# SCH_LIGA2026_2026-04-17.net
KiCad netlist of a schematic drawn in EasyEDA
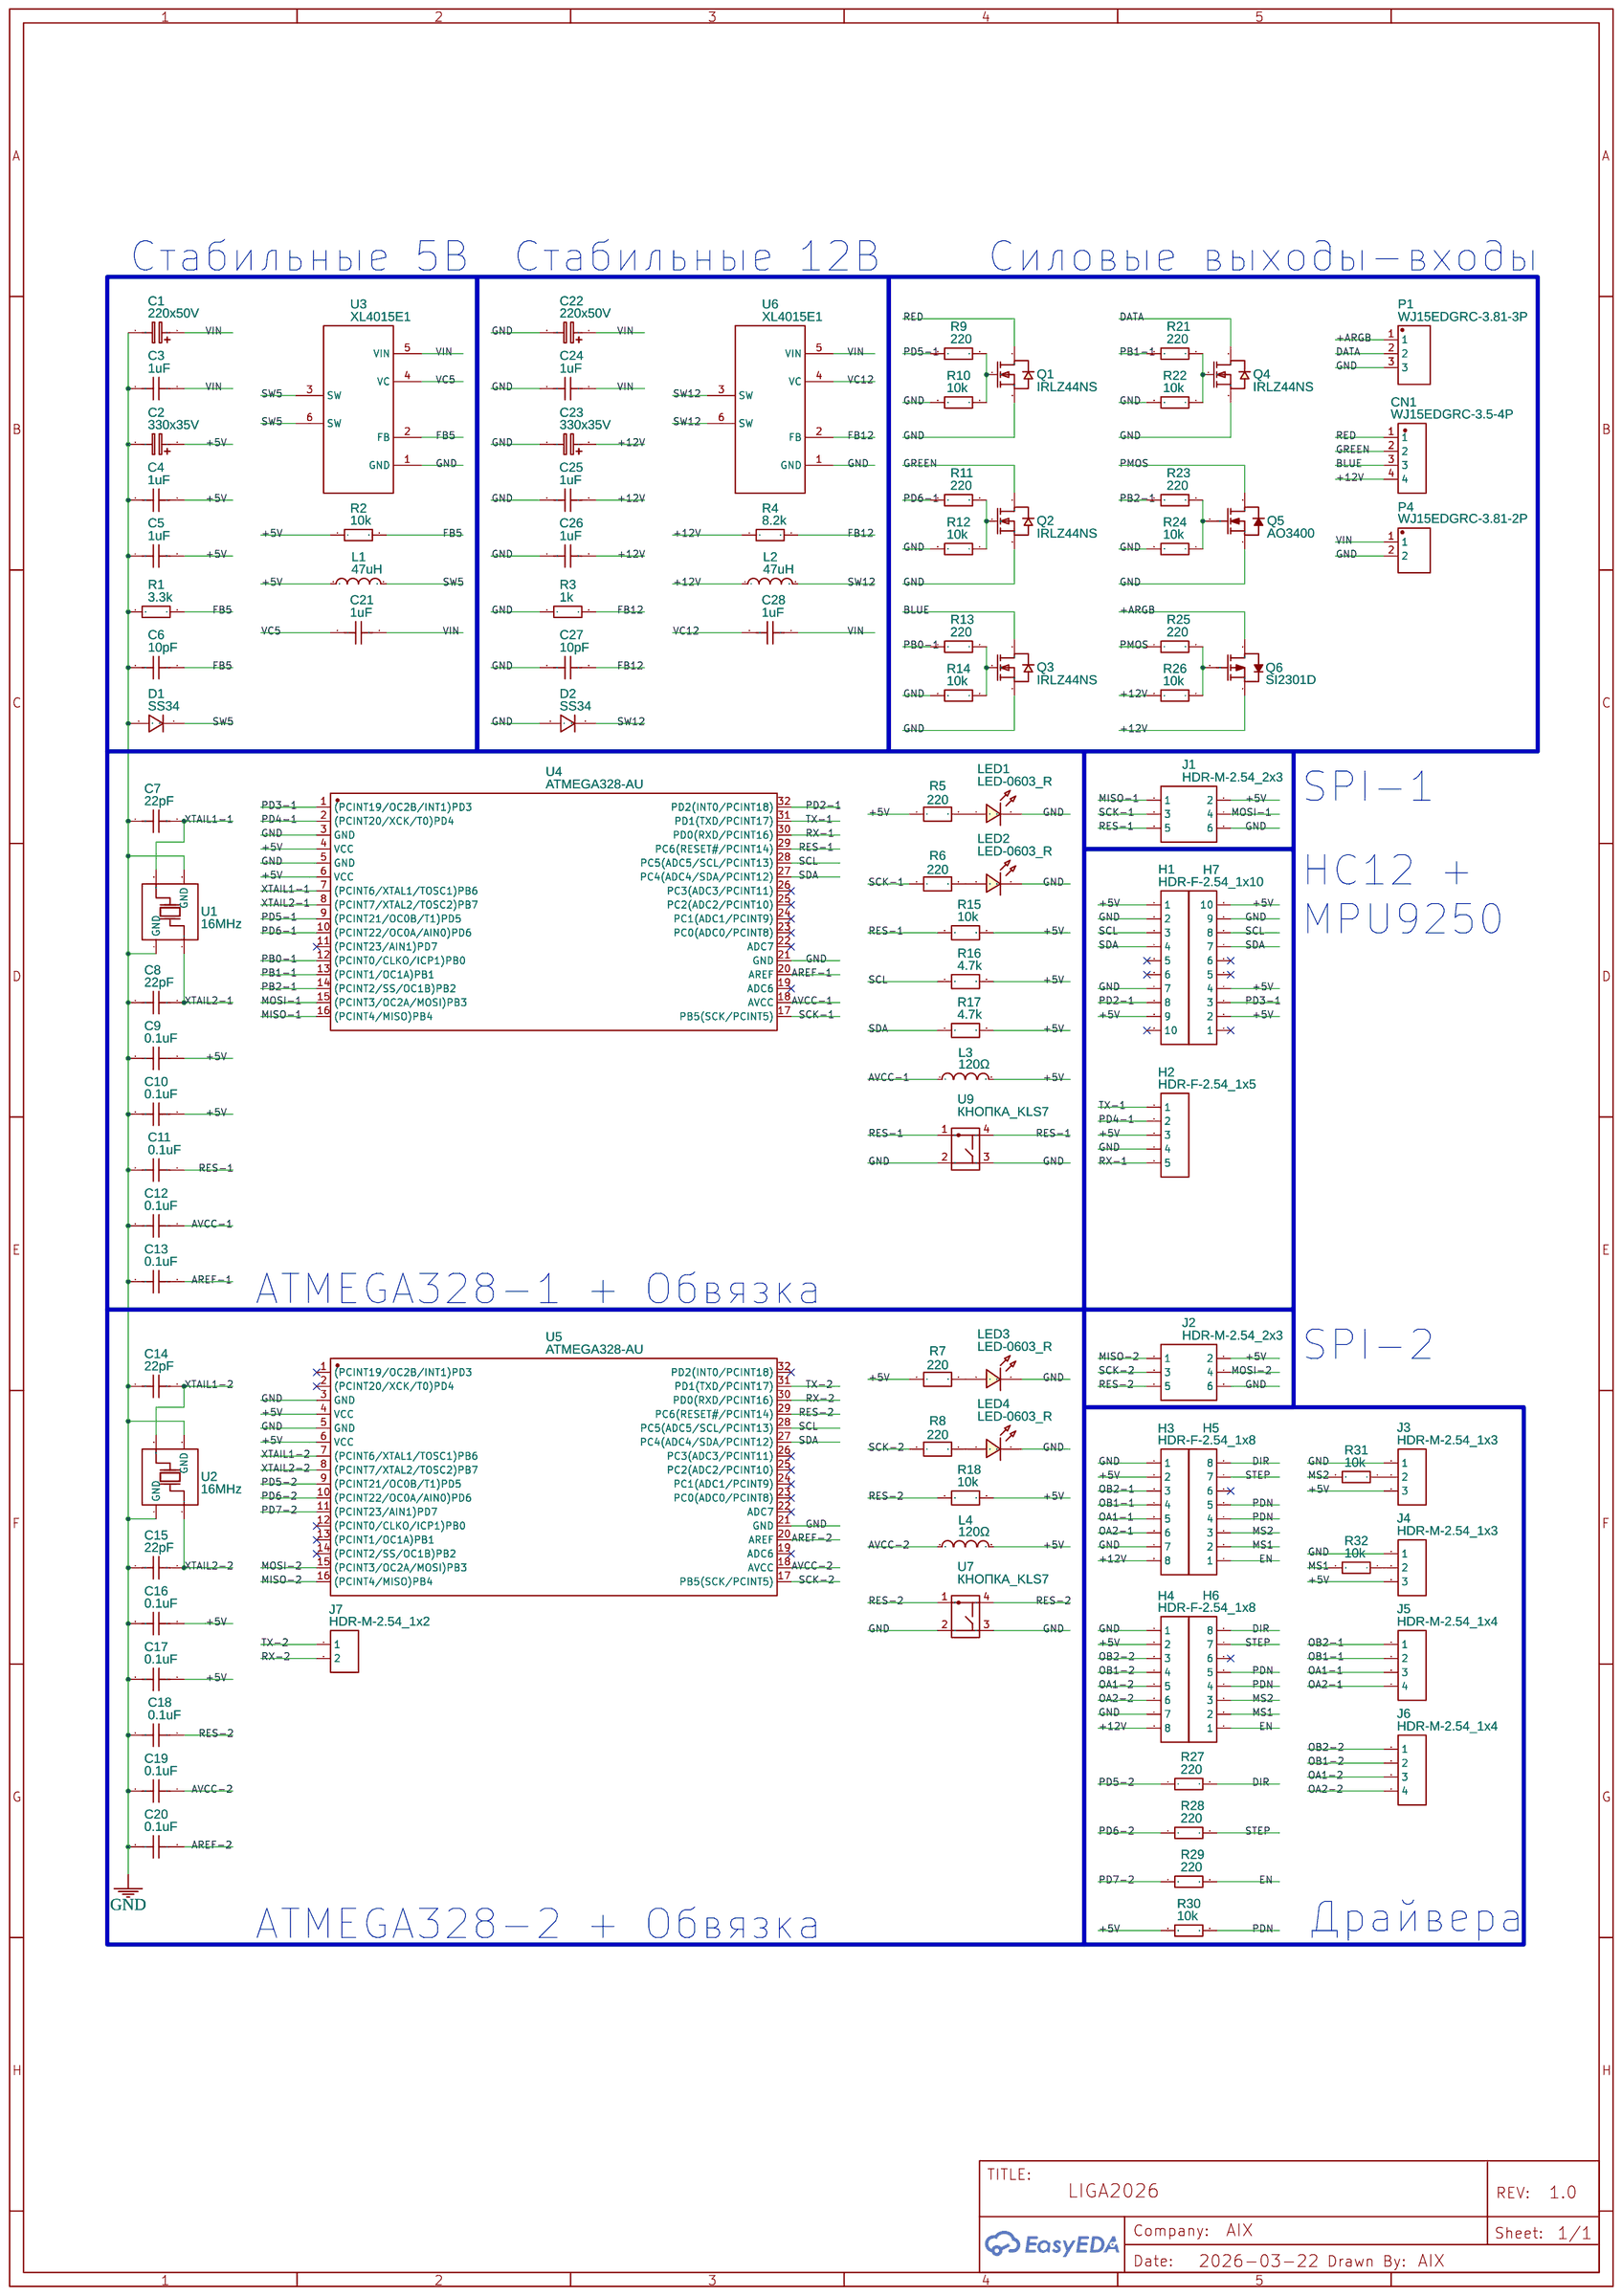
[diagram p0: schematic sheet]

(export (version "E")
  (design (tool "Eeschema 10.0.6"))
  (components
    (comp (ref "C1")
      (value "220x50V")
      (fields (field (name "Manufacturer Part") "330uF 35V (ECAP)"))
      (libsource (lib "") (part "ECAP_SMD_10X10.5"))
    )
    (comp (ref "C2")
      (value "330x35V")
      (fields (field (name "Manufacturer Part") "330uF 35V (ECAP)"))
      (libsource (lib "") (part "ECAP_SMD_10X10.5"))
    )
    (comp (ref "C3")
      (value "1uF")
      (fields (field (name "Manufacturer Part") "0805"))
      (libsource (lib "") (part "0805_C9900012713"))
    )
    (comp (ref "C4")
      (value "1uF")
      (fields (field (name "Manufacturer Part") "0805"))
      (libsource (lib "") (part "0805_C9900012713"))
    )
    (comp (ref "C5")
      (value "1uF")
      (fields (field (name "Manufacturer Part") "0805"))
      (libsource (lib "") (part "0805_C9900012713_1"))
    )
    (comp (ref "C6")
      (value "10pF")
      (fields
        (field (name "Manufacturer Part") "CSA0603C0G100J500JT")
        (field (name "Manufacturer") "HRE(芯声)")
      )
      (libsource (lib "") (part "CSA0603C0G100J500JT"))
    )
    (comp (ref "C7") (value "22pF") (libsource (lib "") (part "C_0603_US_1")))
    (comp (ref "C8") (value "22pF") (libsource (lib "") (part "C_0603_US_1")))
    (comp (ref "C9") (value "0.1uF") (libsource (lib "") (part "C_0603_US")))
    (comp (ref "C10") (value "0.1uF") (libsource (lib "") (part "C_0603_US")))
    (comp (ref "C11") (value "0.1uF") (libsource (lib "") (part "C_0603_US")))
    (comp (ref "C12") (value "0.1uF") (libsource (lib "") (part "C_0603_US")))
    (comp (ref "C13") (value "0.1uF") (libsource (lib "") (part "C_0603_US")))
    (comp (ref "C14") (value "22pF") (libsource (lib "") (part "C_0603_US_1")))
    (comp (ref "C15") (value "22pF") (libsource (lib "") (part "C_0603_US_1")))
    (comp (ref "C16") (value "0.1uF") (libsource (lib "") (part "C_0603_US")))
    (comp (ref "C17") (value "0.1uF") (libsource (lib "") (part "C_0603_US")))
    (comp (ref "C18") (value "0.1uF") (libsource (lib "") (part "C_0603_US")))
    (comp (ref "C19") (value "0.1uF") (libsource (lib "") (part "C_0603_US")))
    (comp (ref "C20") (value "0.1uF") (libsource (lib "") (part "C_0603_US")))
    (comp (ref "C21")
      (value "1uF")
      (fields (field (name "Manufacturer Part") "0805"))
      (libsource (lib "") (part "0805_C9900012713"))
    )
    (comp (ref "C22")
      (value "220x50V")
      (fields (field (name "Manufacturer Part") "330uF 35V (ECAP)"))
      (libsource (lib "") (part "ECAP_SMD_10X10.5_1"))
    )
    (comp (ref "C23")
      (value "330x35V")
      (fields (field (name "Manufacturer Part") "330uF 35V (ECAP)"))
      (libsource (lib "") (part "ECAP_SMD_10X10.5_1"))
    )
    (comp (ref "C24")
      (value "1uF")
      (fields (field (name "Manufacturer Part") "0805"))
      (libsource (lib "") (part "0805_C9900012713"))
    )
    (comp (ref "C25")
      (value "1uF")
      (fields (field (name "Manufacturer Part") "0805"))
      (libsource (lib "") (part "0805_C9900012713"))
    )
    (comp (ref "C26")
      (value "1uF")
      (fields (field (name "Manufacturer Part") "0805"))
      (libsource (lib "") (part "0805_C9900012713_1"))
    )
    (comp (ref "C27")
      (value "10pF")
      (fields
        (field (name "Manufacturer Part") "CSA0603C0G100J500JT")
        (field (name "Manufacturer") "HRE(芯声)")
      )
      (libsource (lib "") (part "CSA0603C0G100J500JT"))
    )
    (comp (ref "C28")
      (value "1uF")
      (fields (field (name "Manufacturer Part") "0805"))
      (libsource (lib "") (part "0805_C9900012713"))
    )
    (comp (ref "CN1")
      (value "WJ15EDGRC-3.5-4P")
      (fields (field (name "Manufacturer") "KANGNEX(康奈克斯电气)"))
      (libsource (lib "") (part "WJ15EDGRC-3.5-4P"))
    )
    (comp (ref "D1")
      (value "SS34")
      (fields (field (name "Manufacturer Part") "1N4007W") (field (name "Manufacturer") "BLUE ROCKET"))
      (libsource (lib "") (part "1N4007W"))
    )
    (comp (ref "D2")
      (value "SS34")
      (fields (field (name "Manufacturer Part") "1N4007W") (field (name "Manufacturer") "BLUE ROCKET"))
      (libsource (lib "") (part "1N4007W"))
    )
    (comp (ref "H1") (value "HDR-F-2.54_1x10") (libsource (lib "") (part "HDR-F-2.54_1x10_1")))
    (comp (ref "H2") (value "HDR-F-2.54_1x5") (libsource (lib "") (part "HDR-F-2.54_1x5")))
    (comp (ref "H3") (value "HDR-F-2.54_1x8") (libsource (lib "") (part "HDR-F-2.54_1x8")))
    (comp (ref "H4") (value "HDR-F-2.54_1x8") (libsource (lib "") (part "HDR-F-2.54_1x8")))
    (comp (ref "H5") (value "HDR-F-2.54_1x8") (libsource (lib "") (part "HDR-F-2.54_1x8_1")))
    (comp (ref "H6") (value "HDR-F-2.54_1x8") (libsource (lib "") (part "HDR-F-2.54_1x8_1")))
    (comp (ref "H7") (value "HDR-F-2.54_1x10") (libsource (lib "") (part "HDR-F-2.54_1x10")))
    (comp (ref "J1") (value "HDR-M-2.54_2x3") (libsource (lib "") (part "HDR-M-2.54_2x3")))
    (comp (ref "J2") (value "HDR-M-2.54_2x3") (libsource (lib "") (part "HDR-M-2.54_2x3")))
    (comp (ref "J3") (value "HDR-M-2.54_1x3") (libsource (lib "") (part "HDR-M-2.54_1x3")))
    (comp (ref "J4") (value "HDR-M-2.54_1x3") (libsource (lib "") (part "HDR-M-2.54_1x3")))
    (comp (ref "J5") (value "HDR-M-2.54_1x4") (libsource (lib "") (part "HDR-M-2.54_1x4")))
    (comp (ref "J6") (value "HDR-M-2.54_1x4") (libsource (lib "") (part "HDR-M-2.54_1x4")))
    (comp (ref "J7") (value "HDR-M-2.54_1x2") (libsource (lib "") (part "HDR-M-2.54_1x2")))
    (comp (ref "L1")
      (value "47uH")
      (fields (field (name "Manufacturer Part") "MDE1040-2R2M") (field (name "Manufacturer") "KOHERelec(科或)"))
      (libsource (lib "") (part "MDE1040-2R2M"))
    )
    (comp (ref "L2")
      (value "47uH")
      (fields (field (name "Manufacturer Part") "MDE1040-2R2M") (field (name "Manufacturer") "KOHERelec(科或)"))
      (libsource (lib "") (part "MDE1040-2R2M"))
    )
    (comp (ref "L3")
      (value "120Ω")
      (fields (field (name "Manufacturer Part") "BLM21PG121SN1D") (field (name "Manufacturer") "muRata(村田)"))
      (libsource (lib "") (part "BLM21PG121SN1D"))
    )
    (comp (ref "L4")
      (value "120Ω")
      (fields (field (name "Manufacturer Part") "BLM21PG121SN1D") (field (name "Manufacturer") "muRata(村田)"))
      (libsource (lib "") (part "BLM21PG121SN1D"))
    )
    (comp (ref "LED1")
      (value "LED-0603_R")
      (fields
        (field (name "Manufacturer Part") "19-217/R6C-AL1M2VY/3T")
        (field (name "Manufacturer") "EVERLIGHT(台湾亿光)")
      )
      (libsource (lib "") (part "LED-0603_R"))
    )
    (comp (ref "LED2")
      (value "LED-0603_R")
      (fields
        (field (name "Manufacturer Part") "19-217/R6C-AL1M2VY/3T")
        (field (name "Manufacturer") "EVERLIGHT(台湾亿光)")
      )
      (libsource (lib "") (part "LED-0603_R"))
    )
    (comp (ref "LED3")
      (value "LED-0603_R")
      (fields
        (field (name "Manufacturer Part") "19-217/R6C-AL1M2VY/3T")
        (field (name "Manufacturer") "EVERLIGHT(台湾亿光)")
      )
      (libsource (lib "") (part "LED-0603_R_1"))
    )
    (comp (ref "LED4")
      (value "LED-0603_R")
      (fields
        (field (name "Manufacturer Part") "19-217/R6C-AL1M2VY/3T")
        (field (name "Manufacturer") "EVERLIGHT(台湾亿光)")
      )
      (libsource (lib "") (part "LED-0603_R_1"))
    )
    (comp (ref "P1")
      (value "WJ15EDGRC-3.81-3P")
      (fields
        (field (name "Manufacturer Part") "WJ15EDGRC-3.81-03P-14-00A")
        (field (name "Manufacturer") "KANGNEX(康奈克斯电气)")
      )
      (libsource (lib "") (part "WJ15EDGRC-3.81-3P"))
    )
    (comp (ref "P4")
      (value "WJ15EDGRC-3.81-2P")
      (fields
        (field (name "Manufacturer Part") "WJ15EDGRC-3.81-02P-14-00A")
        (field (name "Manufacturer") "KANGNEX(康奈克斯电气)")
      )
      (libsource (lib "") (part "WJ15EDGRC-3.81-2P"))
    )
    (comp (ref "Q1")
      (value "IRLZ44NS")
      (fields
        (field (name "Manufacturer Part") "IRLZ44NSTRL(UMW)")
        (field (name "Manufacturer") "UMW(友台半导体)")
      )
      (libsource (lib "") (part "IRLZ44NSTRL(UMW)"))
    )
    (comp (ref "Q2")
      (value "IRLZ44NS")
      (fields
        (field (name "Manufacturer Part") "IRLZ44NSTRL(UMW)")
        (field (name "Manufacturer") "UMW(友台半导体)")
      )
      (libsource (lib "") (part "IRLZ44NSTRL(UMW)"))
    )
    (comp (ref "Q3")
      (value "IRLZ44NS")
      (fields
        (field (name "Manufacturer Part") "IRLZ44NSTRL(UMW)")
        (field (name "Manufacturer") "UMW(友台半导体)")
      )
      (libsource (lib "") (part "IRLZ44NSTRL(UMW)"))
    )
    (comp (ref "Q4")
      (value "IRLZ44NS")
      (fields
        (field (name "Manufacturer Part") "IRLZ44NSTRL(UMW)")
        (field (name "Manufacturer") "UMW(友台半导体)")
      )
      (libsource (lib "") (part "IRLZ44NSTRL(UMW)"))
    )
    (comp (ref "Q5")
      (value "AO3400")
      (fields (field (name "Manufacturer Part") "AO3400A") (field (name "Manufacturer") "ChipNobo(无边界)"))
      (libsource (lib "") (part "AO3400A_C42419946"))
    )
    (comp (ref "Q6")
      (value "SI2301D")
      (fields (field (name "Manufacturer Part") "SI2301DS-ES") (field (name "Manufacturer") "ElecSuper(静芯)"))
      (libsource (lib "") (part "SI2301DS-ES"))
    )
    (comp (ref "R1")
      (value "3.3k")
      (fields (field (name "Manufacturer Part") "0805"))
      (libsource (lib "") (part "0805_C9900012714"))
    )
    (comp (ref "R2")
      (value "10k")
      (fields (field (name "Manufacturer Part") "0805"))
      (libsource (lib "") (part "0805_C9900012714"))
    )
    (comp (ref "R3")
      (value "1k")
      (fields (field (name "Manufacturer Part") "0805"))
      (libsource (lib "") (part "0805_C9900012714"))
    )
    (comp (ref "R4")
      (value "8.2k")
      (fields (field (name "Manufacturer Part") "0805"))
      (libsource (lib "") (part "0805_C9900012714"))
    )
    (comp (ref "R5") (value "220") (libsource (lib "") (part "R_0603_EU")))
    (comp (ref "R6") (value "220") (libsource (lib "") (part "R_0603_EU")))
    (comp (ref "R7") (value "220") (libsource (lib "") (part "R_0603_EU")))
    (comp (ref "R8") (value "220") (libsource (lib "") (part "R_0603_EU")))
    (comp (ref "R9")
      (value "220")
      (fields (field (name "Manufacturer Part") "0805"))
      (libsource (lib "") (part "0805_C9900012714"))
    )
    (comp (ref "R10")
      (value "10k")
      (fields (field (name "Manufacturer Part") "0805"))
      (libsource (lib "") (part "0805_C9900012714_1"))
    )
    (comp (ref "R11")
      (value "220")
      (fields (field (name "Manufacturer Part") "0805"))
      (libsource (lib "") (part "0805_C9900012714"))
    )
    (comp (ref "R12")
      (value "10k")
      (fields (field (name "Manufacturer Part") "0805"))
      (libsource (lib "") (part "0805_C9900012714_1"))
    )
    (comp (ref "R13")
      (value "220")
      (fields (field (name "Manufacturer Part") "0805"))
      (libsource (lib "") (part "0805_C9900012714"))
    )
    (comp (ref "R14")
      (value "10k")
      (fields (field (name "Manufacturer Part") "0805"))
      (libsource (lib "") (part "0805_C9900012714_1"))
    )
    (comp (ref "R15") (value "10k") (libsource (lib "") (part "R_0603_EU")))
    (comp (ref "R16") (value "4.7k") (libsource (lib "") (part "R_0603_EU")))
    (comp (ref "R17") (value "4.7k") (libsource (lib "") (part "R_0603_EU")))
    (comp (ref "R18") (value "10k") (libsource (lib "") (part "R_0603_EU")))
    (comp (ref "R21")
      (value "220")
      (fields (field (name "Manufacturer Part") "0805"))
      (libsource (lib "") (part "0805_C9900012714"))
    )
    (comp (ref "R22")
      (value "10k")
      (fields (field (name "Manufacturer Part") "0805"))
      (libsource (lib "") (part "0805_C9900012714_1"))
    )
    (comp (ref "R23")
      (value "220")
      (fields (field (name "Manufacturer Part") "0805"))
      (libsource (lib "") (part "0805_C9900012714"))
    )
    (comp (ref "R24")
      (value "10k")
      (fields (field (name "Manufacturer Part") "0805"))
      (libsource (lib "") (part "0805_C9900012714_1"))
    )
    (comp (ref "R25")
      (value "220")
      (fields (field (name "Manufacturer Part") "0805"))
      (libsource (lib "") (part "0805_C9900012714"))
    )
    (comp (ref "R26")
      (value "10k")
      (fields (field (name "Manufacturer Part") "0805"))
      (libsource (lib "") (part "0805_C9900012714_1"))
    )
    (comp (ref "R27")
      (value "220")
      (fields (field (name "Manufacturer Part") "0805"))
      (libsource (lib "") (part "0805_C9900012714"))
    )
    (comp (ref "R28")
      (value "220")
      (fields (field (name "Manufacturer Part") "0805"))
      (libsource (lib "") (part "0805_C9900012714"))
    )
    (comp (ref "R29")
      (value "220")
      (fields (field (name "Manufacturer Part") "0805"))
      (libsource (lib "") (part "0805_C9900012714"))
    )
    (comp (ref "R30")
      (value "10k")
      (fields (field (name "Manufacturer Part") "0805"))
      (libsource (lib "") (part "0805_C9900012714_1"))
    )
    (comp (ref "R31")
      (value "10k")
      (fields (field (name "Manufacturer Part") "0805"))
      (libsource (lib "") (part "0805_C9900012714_1"))
    )
    (comp (ref "R32")
      (value "10k")
      (fields (field (name "Manufacturer Part") "0805"))
      (libsource (lib "") (part "0805_C9900012714_1"))
    )
    (comp (ref "U1")
      (value "16MHz")
      (fields
        (field (name "Manufacturer Part") "NX2520SA-16MHZ-EXS00A-CS05116")
        (field (name "Manufacturer") "NDK")
      )
      (libsource (lib "") (part "NX2520SA-16MHZ-EXS00A-CS05116"))
    )
    (comp (ref "U2")
      (value "16MHz")
      (fields
        (field (name "Manufacturer Part") "NX2520SA-16MHZ-EXS00A-CS05116")
        (field (name "Manufacturer") "NDK")
      )
      (libsource (lib "") (part "NX2520SA-16MHZ-EXS00A-CS05116"))
    )
    (comp (ref "U3")
      (value "XL4015E1")
      (fields (field (name "Manufacturer") "XLSEMI(芯龙)"))
      (libsource (lib "") (part "XL4015E1"))
    )
    (comp (ref "U4")
      (value "ATMEGA328-AU")
      (fields (field (name "Manufacturer") "MICROCHIP(美国微芯)"))
      (libsource (lib "") (part "ATMEGA328-AU"))
    )
    (comp (ref "U5")
      (value "ATMEGA328-AU")
      (fields (field (name "Manufacturer") "MICROCHIP(美国微芯)"))
      (libsource (lib "") (part "ATMEGA328-AU"))
    )
    (comp (ref "U6")
      (value "XL4015E1")
      (fields (field (name "Manufacturer") "XLSEMI(芯龙)"))
      (libsource (lib "") (part "XL4015E1"))
    )
    (comp (ref "U7") (value "КНОПКА_KLS7") (libsource (lib "") (part "КНОПКА_KLS7-TS4407-1.5-180")))
    (comp (ref "U9") (value "КНОПКА_KLS7") (libsource (lib "") (part "КНОПКА_KLS7-TS4407-1.5-180")))
  )
  (nets
    (net (code "1") (name "/+5V") (class "Default")
      (node (ref "C10") (pin "1") (pinfunction "1_1") (pintype "unspecified"))
      (node (ref "C16") (pin "1") (pinfunction "1_1") (pintype "unspecified"))
      (node (ref "C17") (pin "1") (pinfunction "1_1") (pintype "unspecified"))
      (node (ref "C2") (pin "1") (pinfunction "1_1") (pintype "unspecified"))
      (node (ref "C4") (pin "1") (pinfunction "1_1") (pintype "unspecified"))
      (node (ref "C5") (pin "2") (pinfunction "2_2") (pintype "unspecified"))
      (node (ref "C9") (pin "1") (pinfunction "1_1") (pintype "unspecified"))
      (node (ref "H1") (pin "1") (pinfunction "1_1") (pintype "unspecified"))
      (node (ref "H1") (pin "9") (pinfunction "9_9") (pintype "unspecified"))
      (node (ref "H2") (pin "3") (pinfunction "3_3") (pintype "unspecified"))
      (node (ref "H3") (pin "2") (pinfunction "2_2") (pintype "unspecified"))
      (node (ref "H4") (pin "2") (pinfunction "2_2") (pintype "unspecified"))
      (node (ref "H7") (pin "10") (pinfunction "10_10") (pintype "unspecified"))
      (node (ref "H7") (pin "2") (pinfunction "2_2") (pintype "unspecified"))
      (node (ref "H7") (pin "4") (pinfunction "4_4") (pintype "unspecified"))
      (node (ref "J1") (pin "2") (pinfunction "2_2") (pintype "input"))
      (node (ref "J2") (pin "2") (pinfunction "2_2") (pintype "input"))
      (node (ref "J3") (pin "3") (pinfunction "3_3") (pintype "input"))
      (node (ref "J4") (pin "3") (pinfunction "3_3") (pintype "input"))
      (node (ref "L1") (pin "1") (pinfunction "1_1") (pintype "unspecified"))
      (node (ref "L3") (pin "2") (pinfunction "2_2") (pintype "unspecified"))
      (node (ref "L4") (pin "2") (pinfunction "2_2") (pintype "unspecified"))
      (node (ref "R15") (pin "2") (pinfunction "2_2") (pintype "unspecified"))
      (node (ref "R16") (pin "2") (pinfunction "2_2") (pintype "unspecified"))
      (node (ref "R17") (pin "2") (pinfunction "2_2") (pintype "unspecified"))
      (node (ref "R18") (pin "2") (pinfunction "2_2") (pintype "unspecified"))
      (node (ref "R2") (pin "1") (pinfunction "1_1") (pintype "unspecified"))
      (node (ref "R30") (pin "2") (pinfunction "2_2") (pintype "unspecified"))
      (node (ref "R5") (pin "1") (pinfunction "1_1") (pintype "unspecified"))
      (node (ref "R7") (pin "1") (pinfunction "1_1") (pintype "unspecified"))
      (node (ref "U4") (pin "4") (pinfunction "VCC_4") (pintype "unspecified"))
      (node (ref "U4") (pin "6") (pinfunction "VCC_6") (pintype "unspecified"))
      (node (ref "U5") (pin "4") (pinfunction "VCC_4") (pintype "unspecified"))
      (node (ref "U5") (pin "6") (pinfunction "VCC_6") (pintype "unspecified"))
    )
    (net (code "2") (name "/+12V") (class "Default")
      (node (ref "C23") (pin "1") (pinfunction "1_1") (pintype "unspecified"))
      (node (ref "C25") (pin "1") (pinfunction "1_1") (pintype "unspecified"))
      (node (ref "C26") (pin "2") (pinfunction "2_2") (pintype "unspecified"))
      (node (ref "CN1") (pin "4") (pinfunction "4_4") (pintype "unspecified"))
      (node (ref "H3") (pin "8") (pinfunction "8_8") (pintype "unspecified"))
      (node (ref "H4") (pin "8") (pinfunction "8_8") (pintype "unspecified"))
      (node (ref "L2") (pin "1") (pinfunction "1_1") (pintype "unspecified"))
      (node (ref "Q6") (pin "2") (pinfunction "S_2") (pintype "unspecified"))
      (node (ref "R26") (pin "2") (pinfunction "2_2") (pintype "unspecified"))
      (node (ref "R4") (pin "1") (pinfunction "1_1") (pintype "unspecified"))
    )
    (net (code "3") (name "/+ARGB") (class "Default")
      (node (ref "P1") (pin "1") (pinfunction "1_1") (pintype "unspecified"))
      (node (ref "Q6") (pin "3") (pinfunction "D_3") (pintype "unspecified"))
    )
    (net (code "4") (name "/AREF-1") (class "Default")
      (node (ref "C13") (pin "1") (pinfunction "1_1") (pintype "unspecified"))
      (node (ref "U4") (pin "20") (pinfunction "AREF_20") (pintype "unspecified"))
    )
    (net (code "5") (name "/AREF-2") (class "Default")
      (node (ref "C20") (pin "1") (pinfunction "1_1") (pintype "unspecified"))
      (node (ref "U5") (pin "20") (pinfunction "AREF_20") (pintype "unspecified"))
    )
    (net (code "6") (name "/AVCC-1") (class "Default")
      (node (ref "C12") (pin "1") (pinfunction "1_1") (pintype "unspecified"))
      (node (ref "L3") (pin "1") (pinfunction "1_1") (pintype "unspecified"))
      (node (ref "U4") (pin "18") (pinfunction "AVCC_18") (pintype "unspecified"))
    )
    (net (code "7") (name "/AVCC-2") (class "Default")
      (node (ref "C19") (pin "1") (pinfunction "1_1") (pintype "unspecified"))
      (node (ref "L4") (pin "1") (pinfunction "1_1") (pintype "unspecified"))
      (node (ref "U5") (pin "18") (pinfunction "AVCC_18") (pintype "unspecified"))
    )
    (net (code "8") (name "/BLUE") (class "Default")
      (node (ref "CN1") (pin "3") (pinfunction "3_3") (pintype "unspecified"))
      (node (ref "Q3") (pin "2") (pinfunction "D_2") (pintype "unspecified"))
    )
    (net (code "9") (name "/DATA") (class "Default")
      (node (ref "P1") (pin "2") (pinfunction "2_2") (pintype "unspecified"))
      (node (ref "Q4") (pin "2") (pinfunction "D_2") (pintype "unspecified"))
    )
    (net (code "10") (name "/DIR") (class "Default")
      (node (ref "H5") (pin "8") (pinfunction "8_8") (pintype "unspecified"))
      (node (ref "H6") (pin "8") (pinfunction "8_8") (pintype "unspecified"))
      (node (ref "R27") (pin "2") (pinfunction "2_2") (pintype "unspecified"))
    )
    (net (code "11") (name "/EN") (class "Default")
      (node (ref "H5") (pin "1") (pinfunction "1_1") (pintype "unspecified"))
      (node (ref "H6") (pin "1") (pinfunction "1_1") (pintype "unspecified"))
      (node (ref "R29") (pin "2") (pinfunction "2_2") (pintype "unspecified"))
    )
    (net (code "12") (name "/FB5") (class "Default")
      (node (ref "C6") (pin "1") (pinfunction "1_1") (pintype "unspecified"))
      (node (ref "R1") (pin "2") (pinfunction "2_2") (pintype "unspecified"))
      (node (ref "R2") (pin "2") (pinfunction "2_2") (pintype "unspecified"))
      (node (ref "U3") (pin "2") (pinfunction "FB_2") (pintype "unspecified"))
    )
    (net (code "13") (name "/FB12") (class "Default")
      (node (ref "C27") (pin "1") (pinfunction "1_1") (pintype "unspecified"))
      (node (ref "R3") (pin "2") (pinfunction "2_2") (pintype "unspecified"))
      (node (ref "R4") (pin "2") (pinfunction "2_2") (pintype "unspecified"))
      (node (ref "U6") (pin "2") (pinfunction "FB_2") (pintype "unspecified"))
    )
    (net (code "14") (name "/GREEN") (class "Default")
      (node (ref "CN1") (pin "2") (pinfunction "2_2") (pintype "unspecified"))
      (node (ref "Q2") (pin "2") (pinfunction "D_2") (pintype "unspecified"))
    )
    (net (code "15") (name "/MISO-1") (class "Default")
      (node (ref "J1") (pin "1") (pinfunction "1_1") (pintype "input"))
      (node (ref "U4") (pin "16") (pinfunction "(PCINT4/MISO)PB4_16") (pintype "unspecified"))
    )
    (net (code "16") (name "/MISO-2") (class "Default")
      (node (ref "J2") (pin "1") (pinfunction "1_1") (pintype "input"))
      (node (ref "U5") (pin "16") (pinfunction "(PCINT4/MISO)PB4_16") (pintype "unspecified"))
    )
    (net (code "17") (name "/MOSI-1") (class "Default")
      (node (ref "J1") (pin "4") (pinfunction "4_4") (pintype "input"))
      (node (ref "U4") (pin "15") (pinfunction "(PCINT3/OC2A/MOSI)PB3_15") (pintype "unspecified"))
    )
    (net (code "18") (name "/MOSI-2") (class "Default")
      (node (ref "J2") (pin "4") (pinfunction "4_4") (pintype "input"))
      (node (ref "U5") (pin "15") (pinfunction "(PCINT3/OC2A/MOSI)PB3_15") (pintype "unspecified"))
    )
    (net (code "19") (name "/MS1") (class "Default")
      (node (ref "H5") (pin "2") (pinfunction "2_2") (pintype "unspecified"))
      (node (ref "H6") (pin "2") (pinfunction "2_2") (pintype "unspecified"))
      (node (ref "R32") (pin "2") (pinfunction "2_2") (pintype "unspecified"))
    )
    (net (code "20") (name "/MS2") (class "Default")
      (node (ref "H5") (pin "3") (pinfunction "3_3") (pintype "unspecified"))
      (node (ref "H6") (pin "3") (pinfunction "3_3") (pintype "unspecified"))
      (node (ref "R31") (pin "2") (pinfunction "2_2") (pintype "unspecified"))
    )
    (net (code "21") (name "/OA1-1") (class "Default")
      (node (ref "H3") (pin "5") (pinfunction "5_5") (pintype "unspecified"))
      (node (ref "J5") (pin "3") (pinfunction "3_3") (pintype "unspecified"))
    )
    (net (code "22") (name "/OA1-2") (class "Default")
      (node (ref "H4") (pin "5") (pinfunction "5_5") (pintype "unspecified"))
      (node (ref "J6") (pin "3") (pinfunction "3_3") (pintype "unspecified"))
    )
    (net (code "23") (name "/OA2-1") (class "Default")
      (node (ref "H3") (pin "6") (pinfunction "6_6") (pintype "unspecified"))
      (node (ref "J5") (pin "4") (pinfunction "4_4") (pintype "unspecified"))
    )
    (net (code "24") (name "/OA2-2") (class "Default")
      (node (ref "H4") (pin "6") (pinfunction "6_6") (pintype "unspecified"))
      (node (ref "J6") (pin "4") (pinfunction "4_4") (pintype "unspecified"))
    )
    (net (code "25") (name "/OB1-1") (class "Default")
      (node (ref "H3") (pin "4") (pinfunction "4_4") (pintype "unspecified"))
      (node (ref "J5") (pin "2") (pinfunction "2_2") (pintype "unspecified"))
    )
    (net (code "26") (name "/OB1-2") (class "Default")
      (node (ref "H4") (pin "4") (pinfunction "4_4") (pintype "unspecified"))
      (node (ref "J6") (pin "2") (pinfunction "2_2") (pintype "unspecified"))
    )
    (net (code "27") (name "/OB2-1") (class "Default")
      (node (ref "H3") (pin "3") (pinfunction "3_3") (pintype "unspecified"))
      (node (ref "J5") (pin "1") (pinfunction "1_1") (pintype "unspecified"))
    )
    (net (code "28") (name "/OB2-2") (class "Default")
      (node (ref "H4") (pin "3") (pinfunction "3_3") (pintype "unspecified"))
      (node (ref "J6") (pin "1") (pinfunction "1_1") (pintype "unspecified"))
    )
    (net (code "29") (name "/PB0-1") (class "Default")
      (node (ref "R13") (pin "1") (pinfunction "1_1") (pintype "unspecified"))
      (node (ref "U4") (pin "12") (pinfunction "(PCINT0/CLKO/ICP1)PB0_12") (pintype "unspecified"))
    )
    (net (code "30") (name "/PB1-1") (class "Default")
      (node (ref "R21") (pin "1") (pinfunction "1_1") (pintype "unspecified"))
      (node (ref "U4") (pin "13") (pinfunction "(PCINT1/OC1A)PB1_13") (pintype "unspecified"))
    )
    (net (code "31") (name "/PB2-1") (class "Default")
      (node (ref "R23") (pin "1") (pinfunction "1_1") (pintype "unspecified"))
      (node (ref "U4") (pin "14") (pinfunction "(PCINT2/SS/OC1B)PB2_14") (pintype "unspecified"))
    )
    (net (code "32") (name "/PD2-1") (class "Default")
      (node (ref "H1") (pin "8") (pinfunction "8_8") (pintype "unspecified"))
      (node (ref "U4") (pin "32") (pinfunction "PD2(INT0/PCINT18)_32") (pintype "unspecified"))
    )
    (net (code "33") (name "/PD3-1") (class "Default")
      (node (ref "H7") (pin "3") (pinfunction "3_3") (pintype "unspecified"))
      (node (ref "U4") (pin "1") (pinfunction "(PCINT19/OC2B/INT1)PD3_1") (pintype "unspecified"))
    )
    (net (code "34") (name "/PD4-1") (class "Default")
      (node (ref "H2") (pin "2") (pinfunction "2_2") (pintype "unspecified"))
      (node (ref "U4") (pin "2") (pinfunction "(PCINT20/XCK/T0)PD4_2") (pintype "unspecified"))
    )
    (net (code "35") (name "/PD5-1") (class "Default")
      (node (ref "R9") (pin "1") (pinfunction "1_1") (pintype "unspecified"))
      (node (ref "U4") (pin "9") (pinfunction "(PCINT21/OC0B/T1)PD5_9") (pintype "unspecified"))
    )
    (net (code "36") (name "/PD5-2") (class "Default")
      (node (ref "R27") (pin "1") (pinfunction "1_1") (pintype "unspecified"))
      (node (ref "U5") (pin "9") (pinfunction "(PCINT21/OC0B/T1)PD5_9") (pintype "unspecified"))
    )
    (net (code "37") (name "/PD6-1") (class "Default")
      (node (ref "R11") (pin "1") (pinfunction "1_1") (pintype "unspecified"))
      (node (ref "U4") (pin "10") (pinfunction "(PCINT22/OC0A/AIN0)PD6_10") (pintype "unspecified"))
    )
    (net (code "38") (name "/PD6-2") (class "Default")
      (node (ref "R28") (pin "1") (pinfunction "1_1") (pintype "unspecified"))
      (node (ref "U5") (pin "10") (pinfunction "(PCINT22/OC0A/AIN0)PD6_10") (pintype "unspecified"))
    )
    (net (code "39") (name "/PD7-2") (class "Default")
      (node (ref "R29") (pin "1") (pinfunction "1_1") (pintype "unspecified"))
      (node (ref "U5") (pin "11") (pinfunction "(PCINT23/AIN1)PD7_11") (pintype "unspecified"))
    )
    (net (code "40") (name "/PDN") (class "Default")
      (node (ref "H5") (pin "4") (pinfunction "4_4") (pintype "unspecified"))
      (node (ref "H5") (pin "5") (pinfunction "5_5") (pintype "unspecified"))
      (node (ref "H6") (pin "4") (pinfunction "4_4") (pintype "unspecified"))
      (node (ref "H6") (pin "5") (pinfunction "5_5") (pintype "unspecified"))
      (node (ref "R30") (pin "1") (pinfunction "1_1") (pintype "unspecified"))
    )
    (net (code "41") (name "/PMOS") (class "Default")
      (node (ref "Q5") (pin "3") (pinfunction "D_3") (pintype "unspecified"))
      (node (ref "R25") (pin "1") (pinfunction "1_1") (pintype "unspecified"))
    )
    (net (code "42") (name "/RED") (class "Default")
      (node (ref "CN1") (pin "1") (pinfunction "1_1") (pintype "unspecified"))
      (node (ref "Q1") (pin "2") (pinfunction "D_2") (pintype "unspecified"))
    )
    (net (code "43") (name "/RES-1") (class "Default")
      (node (ref "C11") (pin "1") (pinfunction "1_1") (pintype "unspecified"))
      (node (ref "J1") (pin "5") (pinfunction "5_5") (pintype "input"))
      (node (ref "R15") (pin "1") (pinfunction "1_1") (pintype "unspecified"))
      (node (ref "U4") (pin "29") (pinfunction "PC6(RESET#/PCINT14)_29") (pintype "unspecified"))
      (node (ref "U9") (pin "1") (pinfunction "1_1") (pintype "unspecified"))
      (node (ref "U9") (pin "4") (pinfunction "4_4") (pintype "unspecified"))
    )
    (net (code "44") (name "/RES-2") (class "Default")
      (node (ref "C18") (pin "1") (pinfunction "1_1") (pintype "unspecified"))
      (node (ref "J2") (pin "5") (pinfunction "5_5") (pintype "input"))
      (node (ref "R18") (pin "1") (pinfunction "1_1") (pintype "unspecified"))
      (node (ref "U5") (pin "29") (pinfunction "PC6(RESET#/PCINT14)_29") (pintype "unspecified"))
      (node (ref "U7") (pin "1") (pinfunction "1_1") (pintype "unspecified"))
      (node (ref "U7") (pin "4") (pinfunction "4_4") (pintype "unspecified"))
    )
    (net (code "45") (name "/RX-1") (class "Default")
      (node (ref "H2") (pin "5") (pinfunction "5_5") (pintype "unspecified"))
      (node (ref "U4") (pin "30") (pinfunction "PD0(RXD/PCINT16)_30") (pintype "unspecified"))
    )
    (net (code "46") (name "/RX-2") (class "Default")
      (node (ref "J7") (pin "2") (pinfunction "2_2") (pintype "unspecified"))
      (node (ref "U5") (pin "30") (pinfunction "PD0(RXD/PCINT16)_30") (pintype "unspecified"))
    )
    (net (code "47") (name "/SCK-1") (class "Default")
      (node (ref "J1") (pin "3") (pinfunction "3_3") (pintype "input"))
      (node (ref "R6") (pin "1") (pinfunction "1_1") (pintype "unspecified"))
      (node (ref "U4") (pin "17") (pinfunction "PB5(SCK/PCINT5)_17") (pintype "unspecified"))
    )
    (net (code "48") (name "/SCK-2") (class "Default")
      (node (ref "J2") (pin "3") (pinfunction "3_3") (pintype "input"))
      (node (ref "R8") (pin "1") (pinfunction "1_1") (pintype "unspecified"))
      (node (ref "U5") (pin "17") (pinfunction "PB5(SCK/PCINT5)_17") (pintype "unspecified"))
    )
    (net (code "49") (name "/SCL") (class "Default")
      (node (ref "H1") (pin "3") (pinfunction "3_3") (pintype "unspecified"))
      (node (ref "H7") (pin "8") (pinfunction "8_8") (pintype "unspecified"))
      (node (ref "R16") (pin "1") (pinfunction "1_1") (pintype "unspecified"))
      (node (ref "U4") (pin "28") (pinfunction "PC5(ADC5/SCL/PCINT13)_28") (pintype "unspecified"))
      (node (ref "U5") (pin "28") (pinfunction "PC5(ADC5/SCL/PCINT13)_28") (pintype "unspecified"))
    )
    (net (code "50") (name "/SDA") (class "Default")
      (node (ref "H1") (pin "4") (pinfunction "4_4") (pintype "unspecified"))
      (node (ref "H7") (pin "7") (pinfunction "7_7") (pintype "unspecified"))
      (node (ref "R17") (pin "1") (pinfunction "1_1") (pintype "unspecified"))
      (node (ref "U4") (pin "27") (pinfunction "PC4(ADC4/SDA/PCINT12)_27") (pintype "unspecified"))
      (node (ref "U5") (pin "27") (pinfunction "PC4(ADC4/SDA/PCINT12)_27") (pintype "unspecified"))
    )
    (net (code "51") (name "/STEP") (class "Default")
      (node (ref "H5") (pin "7") (pinfunction "7_7") (pintype "unspecified"))
      (node (ref "H6") (pin "7") (pinfunction "7_7") (pintype "unspecified"))
      (node (ref "R28") (pin "2") (pinfunction "2_2") (pintype "unspecified"))
    )
    (net (code "52") (name "/SW5") (class "Default")
      (node (ref "D1") (pin "2") (pinfunction "2_2") (pintype "unspecified"))
      (node (ref "L1") (pin "2") (pinfunction "2_2") (pintype "unspecified"))
      (node (ref "U3") (pin "3") (pinfunction "SW_3") (pintype "unspecified"))
      (node (ref "U3") (pin "6") (pinfunction "SW_6") (pintype "unspecified"))
    )
    (net (code "53") (name "/SW12") (class "Default")
      (node (ref "D2") (pin "2") (pinfunction "2_2") (pintype "unspecified"))
      (node (ref "L2") (pin "2") (pinfunction "2_2") (pintype "unspecified"))
      (node (ref "U6") (pin "3") (pinfunction "SW_3") (pintype "unspecified"))
      (node (ref "U6") (pin "6") (pinfunction "SW_6") (pintype "unspecified"))
    )
    (net (code "54") (name "/TX-1") (class "Default")
      (node (ref "H2") (pin "1") (pinfunction "1_1") (pintype "unspecified"))
      (node (ref "U4") (pin "31") (pinfunction "PD1(TXD/PCINT17)_31") (pintype "unspecified"))
    )
    (net (code "55") (name "/TX-2") (class "Default")
      (node (ref "J7") (pin "1") (pinfunction "1_1") (pintype "unspecified"))
      (node (ref "U5") (pin "31") (pinfunction "PD1(TXD/PCINT17)_31") (pintype "unspecified"))
    )
    (net (code "56") (name "/VC5") (class "Default")
      (node (ref "C21") (pin "2") (pinfunction "2_2") (pintype "unspecified"))
      (node (ref "U3") (pin "4") (pinfunction "VC_4") (pintype "unspecified"))
    )
    (net (code "57") (name "/VC12") (class "Default")
      (node (ref "C28") (pin "2") (pinfunction "2_2") (pintype "unspecified"))
      (node (ref "U6") (pin "4") (pinfunction "VC_4") (pintype "unspecified"))
    )
    (net (code "58") (name "/VIN") (class "Default")
      (node (ref "C1") (pin "1") (pinfunction "1_1") (pintype "unspecified"))
      (node (ref "C21") (pin "1") (pinfunction "1_1") (pintype "unspecified"))
      (node (ref "C22") (pin "1") (pinfunction "1_1") (pintype "unspecified"))
      (node (ref "C24") (pin "1") (pinfunction "1_1") (pintype "unspecified"))
      (node (ref "C28") (pin "1") (pinfunction "1_1") (pintype "unspecified"))
      (node (ref "C3") (pin "1") (pinfunction "1_1") (pintype "unspecified"))
      (node (ref "P4") (pin "1") (pinfunction "1_1") (pintype "unspecified"))
      (node (ref "U3") (pin "5") (pinfunction "VIN_5") (pintype "unspecified"))
      (node (ref "U6") (pin "5") (pinfunction "VIN_5") (pintype "unspecified"))
    )
    (net (code "59") (name "/XTAIL1-1") (class "Default")
      (node (ref "C7") (pin "2") (pinfunction "2_2") (pintype "unspecified"))
      (node (ref "U1") (pin "3") (pinfunction "OSC2_3") (pintype "input"))
      (node (ref "U4") (pin "7") (pinfunction "(PCINT6/XTAL1/TOSC1)PB6_7") (pintype "unspecified"))
    )
    (net (code "60") (name "/XTAIL1-2") (class "Default")
      (node (ref "C14") (pin "2") (pinfunction "2_2") (pintype "unspecified"))
      (node (ref "U2") (pin "3") (pinfunction "OSC2_3") (pintype "input"))
      (node (ref "U5") (pin "7") (pinfunction "(PCINT6/XTAL1/TOSC1)PB6_7") (pintype "unspecified"))
    )
    (net (code "61") (name "/XTAIL2-1") (class "Default")
      (node (ref "C8") (pin "2") (pinfunction "2_2") (pintype "unspecified"))
      (node (ref "U1") (pin "1") (pinfunction "OSC1_1") (pintype "input"))
      (node (ref "U4") (pin "8") (pinfunction "(PCINT7/XTAL2/TOSC2)PB7_8") (pintype "unspecified"))
    )
    (net (code "62") (name "/XTAIL2-2") (class "Default")
      (node (ref "C15") (pin "2") (pinfunction "2_2") (pintype "unspecified"))
      (node (ref "U2") (pin "1") (pinfunction "OSC1_1") (pintype "input"))
      (node (ref "U5") (pin "8") (pinfunction "(PCINT7/XTAL2/TOSC2)PB7_8") (pintype "unspecified"))
    )
    (net (code "63") (name "GND") (class "Default")
      (node (ref "C1") (pin "2") (pinfunction "2_2") (pintype "unspecified"))
      (node (ref "C10") (pin "2") (pinfunction "2_2") (pintype "unspecified"))
      (node (ref "C11") (pin "2") (pinfunction "2_2") (pintype "unspecified"))
      (node (ref "C12") (pin "2") (pinfunction "2_2") (pintype "unspecified"))
      (node (ref "C13") (pin "2") (pinfunction "2_2") (pintype "unspecified"))
      (node (ref "C14") (pin "1") (pinfunction "1_1") (pintype "unspecified"))
      (node (ref "C15") (pin "1") (pinfunction "1_1") (pintype "unspecified"))
      (node (ref "C16") (pin "2") (pinfunction "2_2") (pintype "unspecified"))
      (node (ref "C17") (pin "2") (pinfunction "2_2") (pintype "unspecified"))
      (node (ref "C18") (pin "2") (pinfunction "2_2") (pintype "unspecified"))
      (node (ref "C19") (pin "2") (pinfunction "2_2") (pintype "unspecified"))
      (node (ref "C2") (pin "2") (pinfunction "2_2") (pintype "unspecified"))
      (node (ref "C20") (pin "2") (pinfunction "2_2") (pintype "unspecified"))
      (node (ref "C22") (pin "2") (pinfunction "2_2") (pintype "unspecified"))
      (node (ref "C23") (pin "2") (pinfunction "2_2") (pintype "unspecified"))
      (node (ref "C24") (pin "2") (pinfunction "2_2") (pintype "unspecified"))
      (node (ref "C25") (pin "2") (pinfunction "2_2") (pintype "unspecified"))
      (node (ref "C26") (pin "1") (pinfunction "1_1") (pintype "unspecified"))
      (node (ref "C27") (pin "2") (pinfunction "2_2") (pintype "unspecified"))
      (node (ref "C3") (pin "2") (pinfunction "2_2") (pintype "unspecified"))
      (node (ref "C4") (pin "2") (pinfunction "2_2") (pintype "unspecified"))
      (node (ref "C5") (pin "1") (pinfunction "1_1") (pintype "unspecified"))
      (node (ref "C6") (pin "2") (pinfunction "2_2") (pintype "unspecified"))
      (node (ref "C7") (pin "1") (pinfunction "1_1") (pintype "unspecified"))
      (node (ref "C8") (pin "1") (pinfunction "1_1") (pintype "unspecified"))
      (node (ref "C9") (pin "2") (pinfunction "2_2") (pintype "unspecified"))
      (node (ref "D1") (pin "1") (pinfunction "1_1") (pintype "unspecified"))
      (node (ref "D2") (pin "1") (pinfunction "1_1") (pintype "unspecified"))
      (node (ref "H1") (pin "2") (pinfunction "2_2") (pintype "unspecified"))
      (node (ref "H1") (pin "7") (pinfunction "7_7") (pintype "unspecified"))
      (node (ref "H2") (pin "4") (pinfunction "4_4") (pintype "unspecified"))
      (node (ref "H3") (pin "1") (pinfunction "1_1") (pintype "unspecified"))
      (node (ref "H3") (pin "7") (pinfunction "7_7") (pintype "unspecified"))
      (node (ref "H4") (pin "1") (pinfunction "1_1") (pintype "unspecified"))
      (node (ref "H4") (pin "7") (pinfunction "7_7") (pintype "unspecified"))
      (node (ref "H7") (pin "9") (pinfunction "9_9") (pintype "unspecified"))
      (node (ref "J1") (pin "6") (pinfunction "6_6") (pintype "input"))
      (node (ref "J2") (pin "6") (pinfunction "6_6") (pintype "input"))
      (node (ref "J3") (pin "1") (pinfunction "1_1") (pintype "input"))
      (node (ref "J4") (pin "1") (pinfunction "1_1") (pintype "input"))
      (node (ref "LED1") (pin "2") (pinfunction "2_2") (pintype "unspecified"))
      (node (ref "LED2") (pin "2") (pinfunction "2_2") (pintype "unspecified"))
      (node (ref "LED3") (pin "2") (pinfunction "2_2") (pintype "unspecified"))
      (node (ref "LED4") (pin "2") (pinfunction "2_2") (pintype "unspecified"))
      (node (ref "P1") (pin "3") (pinfunction "3_3") (pintype "unspecified"))
      (node (ref "P4") (pin "2") (pinfunction "2_2") (pintype "unspecified"))
      (node (ref "Q1") (pin "3") (pinfunction "S_3") (pintype "unspecified"))
      (node (ref "Q2") (pin "3") (pinfunction "S_3") (pintype "unspecified"))
      (node (ref "Q3") (pin "3") (pinfunction "S_3") (pintype "unspecified"))
      (node (ref "Q4") (pin "3") (pinfunction "S_3") (pintype "unspecified"))
      (node (ref "Q5") (pin "2") (pinfunction "S_2") (pintype "unspecified"))
      (node (ref "R1") (pin "1") (pinfunction "1_1") (pintype "unspecified"))
      (node (ref "R10") (pin "2") (pinfunction "2_2") (pintype "unspecified"))
      (node (ref "R12") (pin "2") (pinfunction "2_2") (pintype "unspecified"))
      (node (ref "R14") (pin "2") (pinfunction "2_2") (pintype "unspecified"))
      (node (ref "R22") (pin "2") (pinfunction "2_2") (pintype "unspecified"))
      (node (ref "R24") (pin "2") (pinfunction "2_2") (pintype "unspecified"))
      (node (ref "R3") (pin "1") (pinfunction "1_1") (pintype "unspecified"))
      (node (ref "U1") (pin "2") (pinfunction "GND_2") (pintype "input"))
      (node (ref "U1") (pin "4") (pinfunction "GND_4") (pintype "input"))
      (node (ref "U2") (pin "2") (pinfunction "GND_2") (pintype "input"))
      (node (ref "U2") (pin "4") (pinfunction "GND_4") (pintype "input"))
      (node (ref "U3") (pin "1") (pinfunction "GND_1") (pintype "unspecified"))
      (node (ref "U4") (pin "21") (pinfunction "GND_21") (pintype "unspecified"))
      (node (ref "U4") (pin "3") (pinfunction "GND_3") (pintype "unspecified"))
      (node (ref "U4") (pin "5") (pinfunction "GND_5") (pintype "unspecified"))
      (node (ref "U5") (pin "21") (pinfunction "GND_21") (pintype "unspecified"))
      (node (ref "U5") (pin "3") (pinfunction "GND_3") (pintype "unspecified"))
      (node (ref "U5") (pin "5") (pinfunction "GND_5") (pintype "unspecified"))
      (node (ref "U6") (pin "1") (pinfunction "GND_1") (pintype "unspecified"))
      (node (ref "U7") (pin "2") (pinfunction "2_2") (pintype "unspecified"))
      (node (ref "U7") (pin "3") (pinfunction "3_3") (pintype "unspecified"))
      (node (ref "U9") (pin "2") (pinfunction "2_2") (pintype "unspecified"))
      (node (ref "U9") (pin "3") (pinfunction "3_3") (pintype "unspecified"))
    )
    (net (code "64") (name "Net-(J3-Pad2)") (class "Default")
      (node (ref "J3") (pin "2") (pinfunction "2_2") (pintype "input"))
      (node (ref "R31") (pin "1") (pinfunction "1_1") (pintype "unspecified"))
    )
    (net (code "65") (name "Net-(J4-Pad2)") (class "Default")
      (node (ref "J4") (pin "2") (pinfunction "2_2") (pintype "input"))
      (node (ref "R32") (pin "1") (pinfunction "1_1") (pintype "unspecified"))
    )
    (net (code "66") (name "Net-(LED1-Pad1)") (class "Default")
      (node (ref "LED1") (pin "1") (pinfunction "1_1") (pintype "unspecified"))
      (node (ref "R5") (pin "2") (pinfunction "2_2") (pintype "unspecified"))
    )
    (net (code "67") (name "Net-(LED2-Pad1)") (class "Default")
      (node (ref "LED2") (pin "1") (pinfunction "1_1") (pintype "unspecified"))
      (node (ref "R6") (pin "2") (pinfunction "2_2") (pintype "unspecified"))
    )
    (net (code "68") (name "Net-(LED3-Pad1)") (class "Default")
      (node (ref "LED3") (pin "1") (pinfunction "1_1") (pintype "unspecified"))
      (node (ref "R7") (pin "2") (pinfunction "2_2") (pintype "unspecified"))
    )
    (net (code "69") (name "Net-(LED4-Pad1)") (class "Default")
      (node (ref "LED4") (pin "1") (pinfunction "1_1") (pintype "unspecified"))
      (node (ref "R8") (pin "2") (pinfunction "2_2") (pintype "unspecified"))
    )
    (net (code "70") (name "Net-(Q1-G)") (class "Default")
      (node (ref "Q1") (pin "1") (pinfunction "G_1") (pintype "unspecified"))
      (node (ref "R10") (pin "1") (pinfunction "1_1") (pintype "unspecified"))
      (node (ref "R9") (pin "2") (pinfunction "2_2") (pintype "unspecified"))
    )
    (net (code "71") (name "Net-(Q2-G)") (class "Default")
      (node (ref "Q2") (pin "1") (pinfunction "G_1") (pintype "unspecified"))
      (node (ref "R11") (pin "2") (pinfunction "2_2") (pintype "unspecified"))
      (node (ref "R12") (pin "1") (pinfunction "1_1") (pintype "unspecified"))
    )
    (net (code "72") (name "Net-(Q3-G)") (class "Default")
      (node (ref "Q3") (pin "1") (pinfunction "G_1") (pintype "unspecified"))
      (node (ref "R13") (pin "2") (pinfunction "2_2") (pintype "unspecified"))
      (node (ref "R14") (pin "1") (pinfunction "1_1") (pintype "unspecified"))
    )
    (net (code "73") (name "Net-(Q4-G)") (class "Default")
      (node (ref "Q4") (pin "1") (pinfunction "G_1") (pintype "unspecified"))
      (node (ref "R21") (pin "2") (pinfunction "2_2") (pintype "unspecified"))
      (node (ref "R22") (pin "1") (pinfunction "1_1") (pintype "unspecified"))
    )
    (net (code "74") (name "Net-(Q5-G)") (class "Default")
      (node (ref "Q5") (pin "1") (pinfunction "G_1") (pintype "unspecified"))
      (node (ref "R23") (pin "2") (pinfunction "2_2") (pintype "unspecified"))
      (node (ref "R24") (pin "1") (pinfunction "1_1") (pintype "unspecified"))
    )
    (net (code "75") (name "Net-(Q6-G)") (class "Default")
      (node (ref "Q6") (pin "1") (pinfunction "G_1") (pintype "unspecified"))
      (node (ref "R25") (pin "2") (pinfunction "2_2") (pintype "unspecified"))
      (node (ref "R26") (pin "1") (pinfunction "1_1") (pintype "unspecified"))
    )
    (net (code "76") (name "unconnected-(H1-Pad5)") (class "Default")
      (node (ref "H1") (pin "5") (pinfunction "5_5") (pintype "unspecified+no_connect"))
    )
    (net (code "77") (name "unconnected-(H1-Pad6)") (class "Default")
      (node (ref "H1") (pin "6") (pinfunction "6_6") (pintype "unspecified+no_connect"))
    )
    (net (code "78") (name "unconnected-(H1-Pad10)") (class "Default")
      (node (ref "H1") (pin "10") (pinfunction "10_10") (pintype "unspecified+no_connect"))
    )
    (net (code "79") (name "unconnected-(H5-Pad6)") (class "Default")
      (node (ref "H5") (pin "6") (pinfunction "6_6") (pintype "unspecified+no_connect"))
    )
    (net (code "80") (name "unconnected-(H6-Pad6)") (class "Default")
      (node (ref "H6") (pin "6") (pinfunction "6_6") (pintype "unspecified+no_connect"))
    )
    (net (code "81") (name "unconnected-(H7-Pad1)") (class "Default")
      (node (ref "H7") (pin "1") (pinfunction "1_1") (pintype "unspecified+no_connect"))
    )
    (net (code "82") (name "unconnected-(H7-Pad5)") (class "Default")
      (node (ref "H7") (pin "5") (pinfunction "5_5") (pintype "unspecified+no_connect"))
    )
    (net (code "83") (name "unconnected-(H7-Pad6)") (class "Default")
      (node (ref "H7") (pin "6") (pinfunction "6_6") (pintype "unspecified+no_connect"))
    )
    (net (code "84") (name "unconnected-(U4-(PCINT23{slash}AIN1)PD7-Pad11)") (class "Default")
      (node (ref "U4") (pin "11") (pinfunction "(PCINT23/AIN1)PD7_11") (pintype "unspecified+no_connect"))
    )
    (net (code "85") (name "unconnected-(U4-ADC6-Pad19)") (class "Default")
      (node (ref "U4") (pin "19") (pinfunction "ADC6_19") (pintype "unspecified+no_connect"))
    )
    (net (code "86") (name "unconnected-(U4-ADC7-Pad22)") (class "Default")
      (node (ref "U4") (pin "22") (pinfunction "ADC7_22") (pintype "unspecified+no_connect"))
    )
    (net (code "87") (name "unconnected-(U4-PC0(ADC0{slash}PCINT8)-Pad23)") (class "Default")
      (node (ref "U4") (pin "23") (pinfunction "PC0(ADC0/PCINT8)_23") (pintype "unspecified+no_connect"))
    )
    (net (code "88") (name "unconnected-(U4-PC1(ADC1{slash}PCINT9)-Pad24)") (class "Default")
      (node (ref "U4") (pin "24") (pinfunction "PC1(ADC1/PCINT9)_24") (pintype "unspecified+no_connect"))
    )
    (net (code "89") (name "unconnected-(U4-PC2(ADC2{slash}PCINT10)-Pad25)") (class "Default")
      (node (ref "U4") (pin "25") (pinfunction "PC2(ADC2/PCINT10)_25") (pintype "unspecified+no_connect"))
    )
    (net (code "90") (name "unconnected-(U4-PC3(ADC3{slash}PCINT11)-Pad26)") (class "Default")
      (node (ref "U4") (pin "26") (pinfunction "PC3(ADC3/PCINT11)_26") (pintype "unspecified+no_connect"))
    )
    (net (code "91") (name "unconnected-(U5-(PCINT0{slash}CLKO{slash}ICP1)PB0-Pad12)") (class "Default")
      (node (ref "U5") (pin "12") (pinfunction "(PCINT0/CLKO/ICP1)PB0_12") (pintype "unspecified"))
    )
    (net (code "92") (name "unconnected-(U5-(PCINT1{slash}OC1A)PB1-Pad13)") (class "Default")
      (node (ref "U5") (pin "13") (pinfunction "(PCINT1/OC1A)PB1_13") (pintype "unspecified"))
    )
    (net (code "93") (name "unconnected-(U5-(PCINT2{slash}SS{slash}OC1B)PB2-Pad14)") (class "Default")
      (node (ref "U5") (pin "14") (pinfunction "(PCINT2/SS/OC1B)PB2_14") (pintype "unspecified+no_connect"))
    )
    (net (code "94") (name "unconnected-(U5-(PCINT19{slash}OC2B{slash}INT1)PD3-Pad1)") (class "Default")
      (node (ref "U5") (pin "1") (pinfunction "(PCINT19/OC2B/INT1)PD3_1") (pintype "unspecified+no_connect"))
    )
    (net (code "95") (name "unconnected-(U5-(PCINT20{slash}XCK{slash}T0)PD4-Pad2)") (class "Default")
      (node (ref "U5") (pin "2") (pinfunction "(PCINT20/XCK/T0)PD4_2") (pintype "unspecified+no_connect"))
    )
    (net (code "96") (name "unconnected-(U5-ADC6-Pad19)") (class "Default")
      (node (ref "U5") (pin "19") (pinfunction "ADC6_19") (pintype "unspecified+no_connect"))
    )
    (net (code "97") (name "unconnected-(U5-ADC7-Pad22)") (class "Default")
      (node (ref "U5") (pin "22") (pinfunction "ADC7_22") (pintype "unspecified"))
    )
    (net (code "98") (name "unconnected-(U5-PC0(ADC0{slash}PCINT8)-Pad23)") (class "Default")
      (node (ref "U5") (pin "23") (pinfunction "PC0(ADC0/PCINT8)_23") (pintype "unspecified"))
    )
    (net (code "99") (name "unconnected-(U5-PC1(ADC1{slash}PCINT9)-Pad24)") (class "Default")
      (node (ref "U5") (pin "24") (pinfunction "PC1(ADC1/PCINT9)_24") (pintype "unspecified"))
    )
    (net (code "100") (name "unconnected-(U5-PC2(ADC2{slash}PCINT10)-Pad25)") (class "Default")
      (node (ref "U5") (pin "25") (pinfunction "PC2(ADC2/PCINT10)_25") (pintype "unspecified"))
    )
    (net (code "101") (name "unconnected-(U5-PC3(ADC3{slash}PCINT11)-Pad26)") (class "Default")
      (node (ref "U5") (pin "26") (pinfunction "PC3(ADC3/PCINT11)_26") (pintype "unspecified"))
    )
    (net (code "102") (name "unconnected-(U5-PD2(INT0{slash}PCINT18)-Pad32)") (class "Default")
      (node (ref "U5") (pin "32") (pinfunction "PD2(INT0/PCINT18)_32") (pintype "unspecified+no_connect"))
    )
  )
)
